# 5V0_PCM.net
KiCad netlist of a schematic drawn in Altium Designer
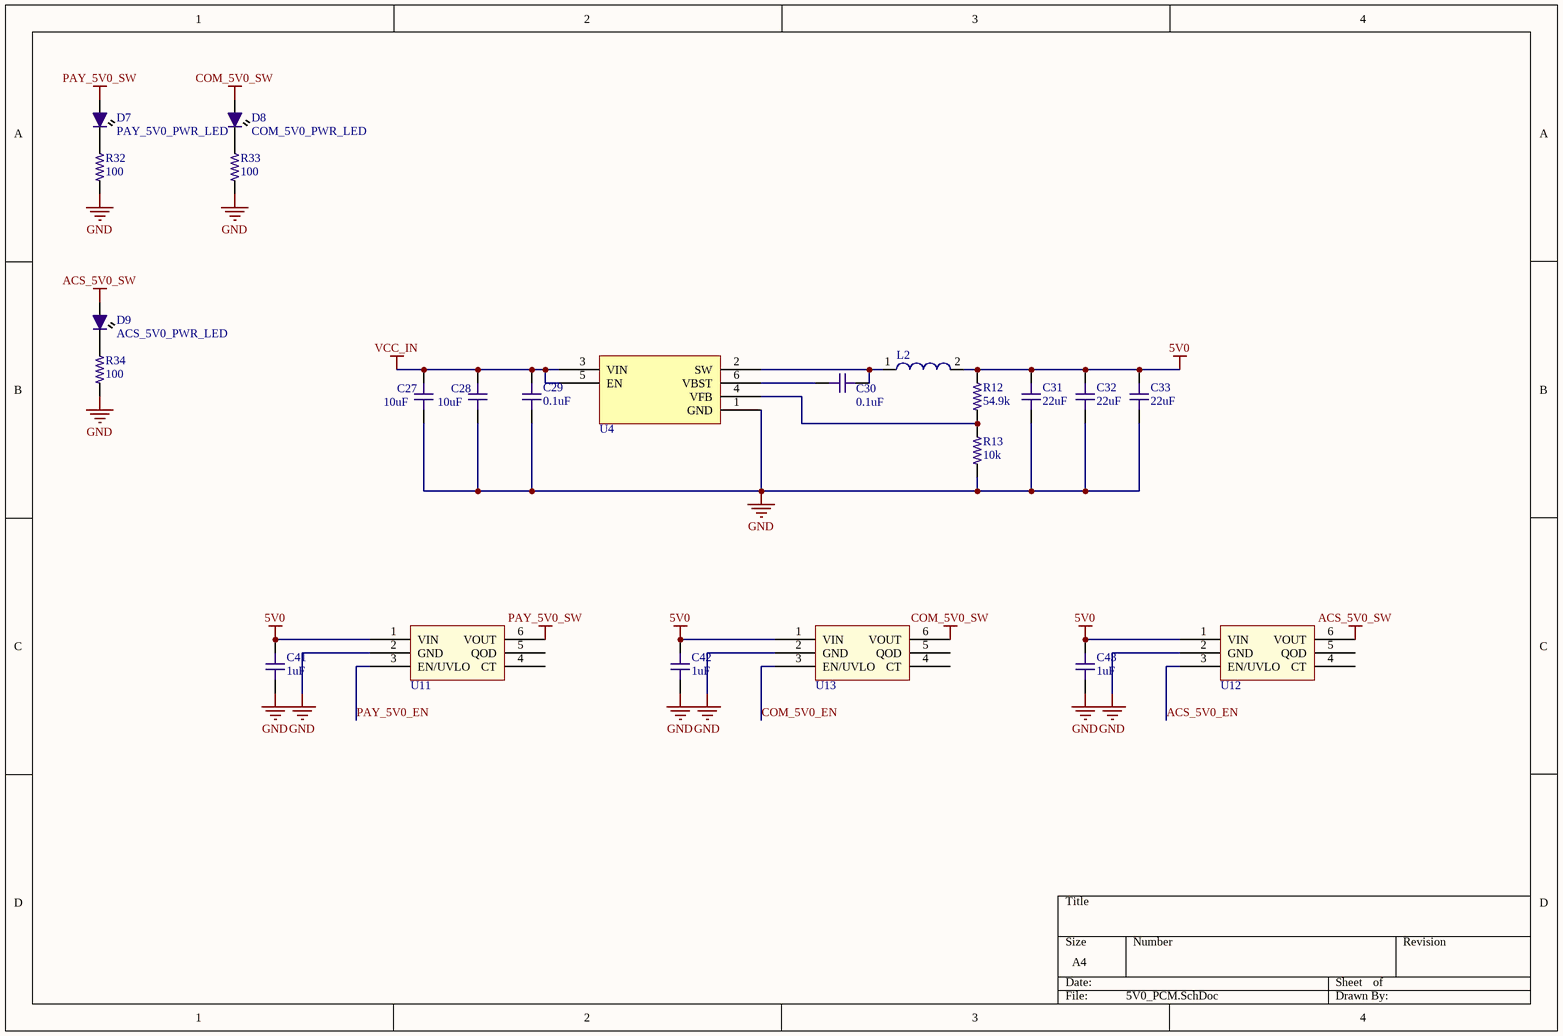
[diagram p0: 5V0_PCM.SchDoc]

(export (version "E")
  (design (tool "Eeschema 10.0.6"))
  (components
    (comp (ref "C27")
      (value "10uF")
      (footprint "C1206-IPC")
      (description "Capacitor (1206) 10uF 25V X5R 1206")
      (fields (field (name "Comment") "Cin"))
      (libsource (lib "UBC_Orbit_Shared_Components") (part "Capacitor"))
    )
    (comp (ref "C28")
      (value "10uF")
      (footprint "C1206-IPC")
      (description "Capacitor (1206) 10uF 25V X5R 1206")
      (fields (field (name "Comment") "Cin"))
      (libsource (lib "UBC_Orbit_Shared_Components") (part "Capacitor"))
    )
    (comp (ref "C29")
      (value "0.1uF")
      (footprint "C0603-IPC")
      (description "Cap Cer 0.1uF 10% 25V Cer Cap X7R 0603")
      (fields (field (name "Comment") "Cinx"))
      (libsource (lib "UBC_Orbit_Shared_Components") (part "Capacitor"))
    )
    (comp (ref "C30")
      (value "0.1uF")
      (footprint "C0603-IPC")
      (description "Cap Cer 0.1uF 10% 25V Cer Cap X7R 0603")
      (fields (field (name "Comment") "Cbst"))
      (libsource (lib "UBC_Orbit_Shared_Components") (part "Capacitor"))
    )
    (comp (ref "C31")
      (value "22uF")
      (footprint "C0603-IPC")
      (description "Cap Cer 22uF 10V X5R 0603")
      (fields (field (name "Comment") "Cout"))
      (libsource (lib "UBC_Orbit_Shared_Components") (part "Capacitor"))
    )
    (comp (ref "C32")
      (value "22uF")
      (footprint "C0603-IPC")
      (description "Cap Cer 22uF 10V X5R 0603")
      (fields (field (name "Comment") "Cout"))
      (libsource (lib "UBC_Orbit_Shared_Components") (part "Capacitor"))
    )
    (comp (ref "C33")
      (value "22uF")
      (footprint "C0603-IPC")
      (description "Cap Cer 22uF 10V X5R 0603")
      (fields (field (name "Comment") "Cout"))
      (libsource (lib "UBC_Orbit_Shared_Components") (part "Capacitor"))
    )
    (comp (ref "C41")
      (value "1uF")
      (footprint "C0603-IPC")
      (description "Capacitor (0603)")
      (fields (field (name "Comment") "Capacitor"))
      (libsource (lib "UBC_Orbit_Shared_Components") (part "Capacitor"))
    )
    (comp (ref "C42")
      (value "1uF")
      (footprint "C0603-IPC")
      (description "Capacitor (0603)")
      (fields (field (name "Comment") "Capacitor"))
      (libsource (lib "UBC_Orbit_Shared_Components") (part "Capacitor"))
    )
    (comp (ref "C43")
      (value "1uF")
      (footprint "C0603-IPC")
      (description "Capacitor (0603)")
      (fields (field (name "Comment") "Capacitor"))
      (libsource (lib "UBC_Orbit_Shared_Components") (part "Capacitor"))
    )
    (comp (ref "D7")
      (value "PAY_5V0_PWR_LED")
      (footprint "LED0603-IPC")
      (description "Red PWR_LED")
      (libsource (lib "Diodes") (part "LED 0603 SMD"))
    )
    (comp (ref "D8")
      (value "COM_5V0_PWR_LED")
      (footprint "LED0603-IPC")
      (description "Red PWR_LED")
      (libsource (lib "Diodes") (part "LED 0603 SMD"))
    )
    (comp (ref "D9")
      (value "ACS_5V0_PWR_LED")
      (footprint "LED0603-IPC")
      (description "Red PWR_LED")
      (libsource (lib "Diodes") (part "LED 0603 SMD"))
    )
    (comp (ref "L2")
      (value "74437349033")
      (footprint "WE-LHMI 7050")
      (description "SMD Power Inductor WE-LHMI, L=3.3 µH")
      (fields (field (name "MANUFACTURER") "Wuerth Elektronik"))
      (libsource (lib "Altium Content Vault") (part "WE-IND-INDUCTOR-2"))
    )
    (comp (ref "R12")
      (value "54.9k")
      (footprint "R0402-IPC")
      (description "54.9k 1% 0402")
      (fields (field (name "Comment") "Rfbt"))
      (libsource (lib "UBC_Orbit_Shared_Components") (part "Resistor"))
    )
    (comp (ref "R13")
      (value "10k")
      (footprint "R0402-IPC")
      (description "10k 1% 0402")
      (fields (field (name "Comment") "Rfbb"))
      (libsource (lib "UBC_Orbit_Shared_Components") (part "Resistor"))
    )
    (comp (ref "R32")
      (value "100")
      (footprint "R0603-IPC")
      (description "Chip Resistor, 0603, 51hms, 0.1W")
      (fields (field (name "Comment") "0603 Template"))
      (libsource (lib "Resistors") (part "0603 Template"))
    )
    (comp (ref "R33")
      (value "100")
      (footprint "R0603-IPC")
      (description "Chip Resistor, 0603, 51hms, 0.1W")
      (fields (field (name "Comment") "0603 Template"))
      (libsource (lib "Resistors") (part "0603 Template"))
    )
    (comp (ref "R34")
      (value "100")
      (footprint "R0603-IPC")
      (description "Chip Resistor, 0603, 51hms, 0.1W")
      (fields (field (name "Comment") "0603 Template"))
      (libsource (lib "Resistors") (part "0603 Template"))
    )
    (comp (ref "U4")
      (value "Buck")
      (footprint "Miscellaneous Devices:SOT23-6_L")
      (description "4.5V tp 17V, 5A Synchronous Step-Down Voltage Regulator")
      (libsource (lib "Integrated_Circuits") (part "TPS565208DDC"))
    )
    (comp (ref "U11")
      (value "One Channel Load Switch")
      (footprint "TPS22810-Q1")
      (description "2.7 - 18V @ 2A Max")
      (libsource (lib "Integrated_Circuits") (part "TPS22810-Q1"))
    )
    (comp (ref "U12")
      (value "One Channel Load Switch")
      (footprint "TPS22810-Q1")
      (description "2.7 - 18V @ 2A Max")
      (libsource (lib "Integrated_Circuits") (part "TPS22810-Q1"))
    )
    (comp (ref "U13")
      (value "One Channel Load Switch")
      (footprint "TPS22810-Q1")
      (description "2.7 - 18V @ 2A Max")
      (libsource (lib "Integrated_Circuits") (part "TPS22810-Q1"))
    )
  )
  (nets
    (net (code "1") (name "/ACS_5V0_EN") (class "Default")
      (node (ref "U12") (pin "3") (pinfunction "EN/UVLO_3") (pintype "passive"))
    )
    (net (code "2") (name "/COM_5V0_EN") (class "Default")
      (node (ref "U13") (pin "3") (pinfunction "EN/UVLO_3") (pintype "passive"))
    )
    (net (code "3") (name "/PAY_5V0_EN") (class "Default")
      (node (ref "U11") (pin "3") (pinfunction "EN/UVLO_3") (pintype "passive"))
    )
    (net (code "4") (name "5V0") (class "Default")
      (node (ref "C31") (pin "2") (pintype "passive"))
      (node (ref "C32") (pin "2") (pintype "passive"))
      (node (ref "C33") (pin "2") (pintype "passive"))
      (node (ref "C41") (pin "2") (pintype "passive"))
      (node (ref "C42") (pin "2") (pintype "passive"))
      (node (ref "C43") (pin "2") (pintype "passive"))
      (node (ref "L2") (pin "2") (pinfunction "2_2") (pintype "passive"))
      (node (ref "R12") (pin "2") (pintype "passive"))
      (node (ref "U11") (pin "1") (pinfunction "VIN_1") (pintype "passive"))
      (node (ref "U12") (pin "1") (pinfunction "VIN_1") (pintype "passive"))
      (node (ref "U13") (pin "1") (pinfunction "VIN_1") (pintype "passive"))
    )
    (net (code "5") (name "ACS_5V0_SW") (class "Default")
      (node (ref "D9") (pin "A") (pintype "passive"))
      (node (ref "U12") (pin "6") (pinfunction "VOUT_6") (pintype "passive"))
    )
    (net (code "6") (name "COM_5V0_SW") (class "Default")
      (node (ref "D8") (pin "A") (pintype "passive"))
      (node (ref "U13") (pin "6") (pinfunction "VOUT_6") (pintype "passive"))
    )
    (net (code "7") (name "GND") (class "Default")
      (node (ref "C27") (pin "1") (pintype "passive"))
      (node (ref "C28") (pin "1") (pintype "passive"))
      (node (ref "C29") (pin "1") (pintype "passive"))
      (node (ref "C31") (pin "1") (pintype "passive"))
      (node (ref "C32") (pin "1") (pintype "passive"))
      (node (ref "C33") (pin "1") (pintype "passive"))
      (node (ref "C41") (pin "1") (pintype "passive"))
      (node (ref "C42") (pin "1") (pintype "passive"))
      (node (ref "C43") (pin "1") (pintype "passive"))
      (node (ref "R13") (pin "1") (pintype "passive"))
      (node (ref "R32") (pin "2") (pintype "passive"))
      (node (ref "R33") (pin "2") (pintype "passive"))
      (node (ref "R34") (pin "2") (pintype "passive"))
      (node (ref "U11") (pin "2") (pinfunction "GND_2") (pintype "passive"))
      (node (ref "U12") (pin "2") (pinfunction "GND_2") (pintype "passive"))
      (node (ref "U13") (pin "2") (pinfunction "GND_2") (pintype "passive"))
      (node (ref "U4") (pin "1") (pinfunction "GND_1") (pintype "passive"))
    )
    (net (code "8") (name "Net-(D7-PadK)") (class "Default")
      (node (ref "D7") (pin "K") (pintype "passive"))
      (node (ref "R32") (pin "1") (pintype "passive"))
    )
    (net (code "9") (name "Net-(D8-PadK)") (class "Default")
      (node (ref "D8") (pin "K") (pintype "passive"))
      (node (ref "R33") (pin "1") (pintype "passive"))
    )
    (net (code "10") (name "Net-(D9-PadK)") (class "Default")
      (node (ref "D9") (pin "K") (pintype "passive"))
      (node (ref "R34") (pin "1") (pintype "passive"))
    )
    (net (code "11") (name "Net-(U4-SW)") (class "Default")
      (node (ref "C30") (pin "2") (pintype "passive"))
      (node (ref "L2") (pin "1") (pinfunction "1_1") (pintype "passive"))
      (node (ref "U4") (pin "2") (pinfunction "SW_2") (pintype "passive"))
    )
    (net (code "12") (name "Net-(U4-VBST)") (class "Default")
      (node (ref "C30") (pin "1") (pintype "passive"))
      (node (ref "U4") (pin "6") (pinfunction "VBST_6") (pintype "passive"))
    )
    (net (code "13") (name "Net-(U4-VFB)") (class "Default")
      (node (ref "R12") (pin "1") (pintype "passive"))
      (node (ref "R13") (pin "2") (pintype "passive"))
      (node (ref "U4") (pin "4") (pinfunction "VFB_4") (pintype "passive"))
    )
    (net (code "14") (name "PAY_5V0_SW") (class "Default")
      (node (ref "D7") (pin "A") (pintype "passive"))
      (node (ref "U11") (pin "6") (pinfunction "VOUT_6") (pintype "passive"))
    )
    (net (code "15") (name "VCC_IN") (class "Default")
      (node (ref "C27") (pin "2") (pintype "passive"))
      (node (ref "C28") (pin "2") (pintype "passive"))
      (node (ref "C29") (pin "2") (pintype "passive"))
      (node (ref "U4") (pin "3") (pinfunction "VIN_3") (pintype "passive"))
      (node (ref "U4") (pin "5") (pinfunction "EN_5") (pintype "passive"))
    )
    (net (code "16") (name "unconnected-(U11-CT-Pad4)") (class "Default")
      (node (ref "U11") (pin "4") (pinfunction "CT_4") (pintype "passive"))
    )
    (net (code "17") (name "unconnected-(U11-QOD-Pad5)") (class "Default")
      (node (ref "U11") (pin "5") (pinfunction "QOD_5") (pintype "passive"))
    )
    (net (code "18") (name "unconnected-(U12-CT-Pad4)") (class "Default")
      (node (ref "U12") (pin "4") (pinfunction "CT_4") (pintype "passive"))
    )
    (net (code "19") (name "unconnected-(U12-QOD-Pad5)") (class "Default")
      (node (ref "U12") (pin "5") (pinfunction "QOD_5") (pintype "passive"))
    )
    (net (code "20") (name "unconnected-(U13-CT-Pad4)") (class "Default")
      (node (ref "U13") (pin "4") (pinfunction "CT_4") (pintype "passive"))
    )
    (net (code "21") (name "unconnected-(U13-QOD-Pad5)") (class "Default")
      (node (ref "U13") (pin "5") (pinfunction "QOD_5") (pintype "passive"))
    )
  )
)
